# 1.net
KiCad netlist of a schematic drawn in EAGLE
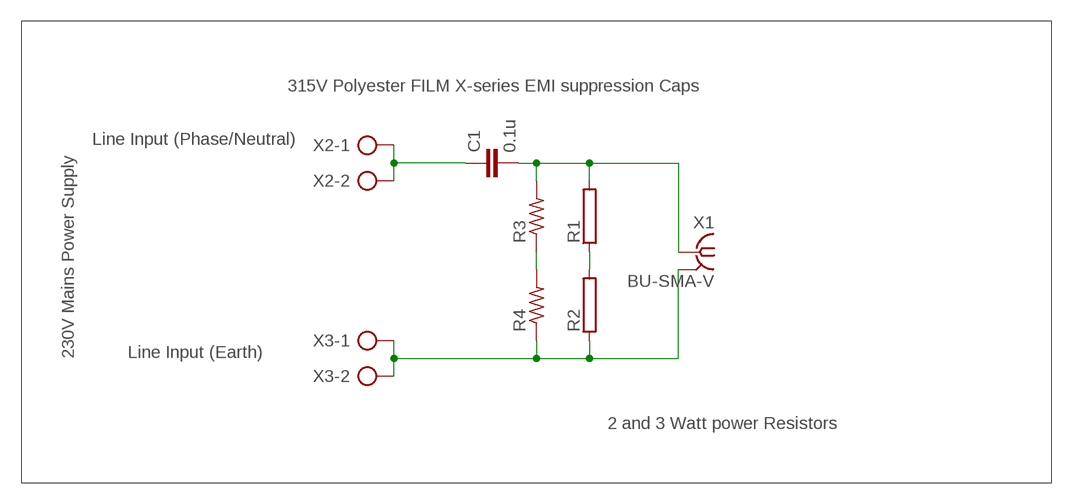
[diagram p0: schematic, sheet 1]

(export (version "E")
  (design (tool "Eeschema 10.0.6"))
  (components
    (comp (ref "C1")
      (value "0.1u")
      (footprint "eagle-import:C15B5")
      (libsource (lib "eagle-import") (part "C15/5"))
    )
    (comp (ref "R1")
      (value "RAC01")
      (footprint "eagle-import:AC01")
      (libsource (lib "eagle-import") (part "RAC01"))
    )
    (comp (ref "R2")
      (value "RAC01")
      (footprint "eagle-import:AC01")
      (libsource (lib "eagle-import") (part "RAC01"))
    )
    (comp (ref "R3")
      (value "R-US_M1206")
      (footprint "eagle-import:M1206")
      (libsource (lib "eagle-import") (part "R-US_M1206"))
    )
    (comp (ref "R4")
      (value "R-US_M1206")
      (footprint "eagle-import:M1206")
      (libsource (lib "eagle-import") (part "R-US_M1206"))
    )
    (comp (ref "X1")
      (value "BU-SMA-V")
      (footprint "eagle-import:BU-SMA-V")
      (libsource (lib "eagle-import") (part "BU-SMA-V"))
    )
    (comp (ref "X2")
      (value "AK500/2")
      (footprint "eagle-import:AK500_2")
      (libsource (lib "eagle-import") (part "AK500/2"))
    )
    (comp (ref "X3")
      (value "AK500/2")
      (footprint "eagle-import:AK500_2")
      (libsource (lib "eagle-import") (part "AK500/2"))
    )
  )
  (nets
    (net (code "1") (name "Net-(C1-Pad2)") (class "Default")
      (node (ref "C1") (pin "2") (pinfunction "2_2") (pintype "passive"))
      (node (ref "R1") (pin "2") (pinfunction "2_2") (pintype "passive"))
      (node (ref "R3") (pin "2") (pinfunction "2_2") (pintype "passive"))
      (node (ref "X1") (pin "1") (pinfunction "1_1") (pintype "passive"))
    )
    (net (code "2") (name "Net-(R1-Pad1)") (class "Default")
      (node (ref "R1") (pin "1") (pinfunction "1_1") (pintype "passive"))
      (node (ref "R2") (pin "2") (pinfunction "2_2") (pintype "passive"))
    )
    (net (code "3") (name "Net-(R3-Pad1)") (class "Default")
      (node (ref "R3") (pin "1") (pinfunction "1_1") (pintype "passive"))
      (node (ref "R4") (pin "2") (pinfunction "2_2") (pintype "passive"))
    )
    (net (code "4") (name "Net-(X1A-GND)") (class "Default")
      (node (ref "R2") (pin "1") (pinfunction "1_1") (pintype "passive"))
      (node (ref "R4") (pin "1") (pinfunction "1_1") (pintype "passive"))
      (node (ref "X1") (pin "2") (pinfunction "GND_2") (pintype "power_in"))
      (node (ref "X3") (pin "1") (pinfunction "KL_1") (pintype "passive"))
      (node (ref "X3") (pin "2") (pinfunction "KL_2") (pintype "passive"))
    )
    (net (code "5") (name "Net-(X2A-KL)") (class "Default")
      (node (ref "C1") (pin "1") (pinfunction "1_1") (pintype "passive"))
      (node (ref "X2") (pin "1") (pinfunction "KL_1") (pintype "passive"))
      (node (ref "X2") (pin "2") (pinfunction "KL_2") (pintype "passive"))
    )
  )
)
